# FRB_Simconex.net
KiCad netlist of a schematic drawn in Altium Designer
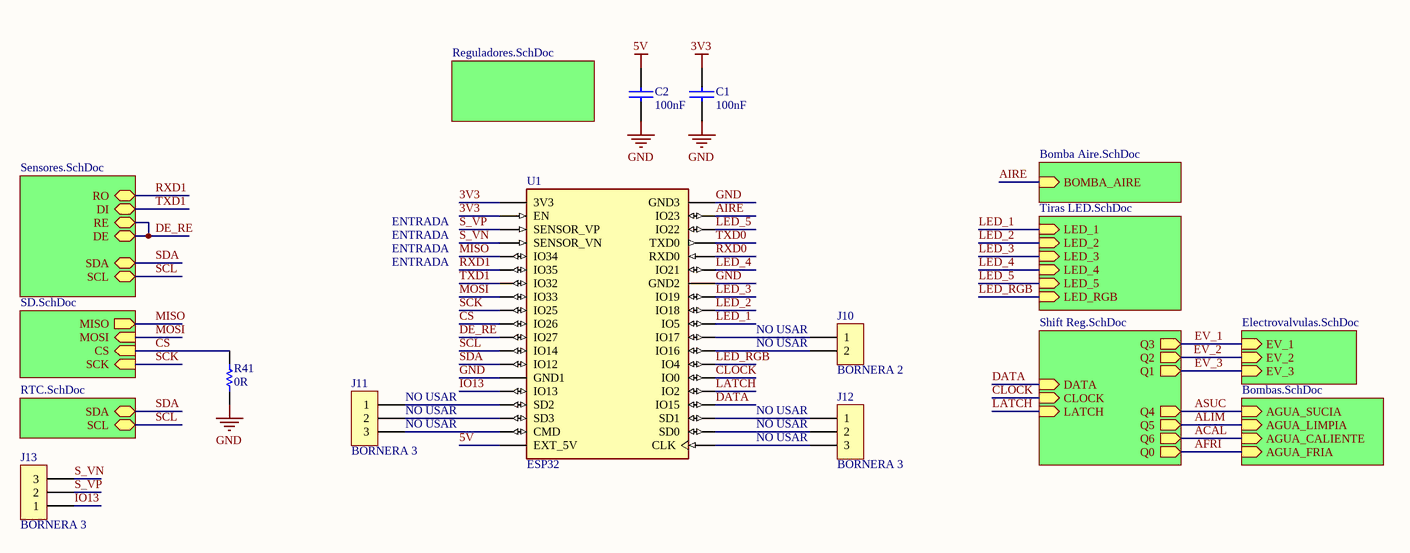
[diagram p0: FRB_Simconex.SchDoc]

(export (version "E")
  (design (tool "Eeschema 10.0.6"))
  (components
    (comp (ref "C1") (value "100nF") (footprint "0805") (libsource (lib "LIBPIOIX") (part "CAP")))
    (comp (ref "C2") (value "100nF") (footprint "0805") (libsource (lib "LIBPIOIX") (part "CAP")))
    (comp (ref "J10")
      (value "BORNERA 2")
      (footprint "BORNERA2")
      (libsource (lib "LIBPIOIX") (part "BORNERA 2"))
    )
    (comp (ref "J11") (value "BORNERA 3") (footprint "BORNERA3") (libsource (lib "") (part "BORNERA 3_2")))
    (comp (ref "J12")
      (value "BORNERA 3")
      (footprint "BORNERA3")
      (libsource (lib "LIBPIOIX") (part "BORNERA 3"))
    )
    (comp (ref "J13") (value "BORNERA 3") (footprint "BORNERA3") (libsource (lib "") (part "BORNERA 3_1")))
    (comp (ref "R41") (value "0R") (footprint "0805") (libsource (lib "LIBPIOIX") (part "RES")))
    (comp (ref "U1") (value "ESP32") (footprint "ESP32") (libsource (lib "Esquematicos") (part "ESP32")))
  )
  (nets
    (net (code "3") (name "/AIRE") (class "Default")
      (node (ref "U1") (pin "J3-2") (pinfunction "IO23_J3-2") (pintype "bidirectional"))
    )
    (net (code "6") (name "/CLOCK") (class "Default")
      (node (ref "U1") (pin "J3-14") (pinfunction "IO0_J3-14") (pintype "bidirectional"))
    )
    (net (code "7") (name "/CS") (class "Default")
      (node (ref "R41") (pin "2") (pinfunction "2_2") (pintype "passive"))
      (node (ref "U1") (pin "J2-10") (pinfunction "IO26_J2-10") (pintype "bidirectional"))
    )
    (net (code "8") (name "/DATA") (class "Default")
      (node (ref "U1") (pin "J3-16") (pinfunction "IO15_J3-16") (pintype "bidirectional"))
    )
    (net (code "9") (name "/DE_RE") (class "Default")
      (node (ref "U1") (pin "J2-11") (pinfunction "IO27_J2-11") (pintype "bidirectional"))
    )
    (net (code "13") (name "/IO13") (class "Default")
      (node (ref "J13") (pin "1") (pinfunction "1_1") (pintype "passive"))
      (node (ref "U1") (pin "J2-15") (pinfunction "IO13_J2-15") (pintype "bidirectional"))
    )
    (net (code "14") (name "/LATCH") (class "Default")
      (node (ref "U1") (pin "J3-15") (pinfunction "IO2_J3-15") (pintype "bidirectional"))
    )
    (net (code "15") (name "/LED_1") (class "Default")
      (node (ref "U1") (pin "J3-10") (pinfunction "IO5_J3-10") (pintype "bidirectional"))
    )
    (net (code "16") (name "/LED_2") (class "Default")
      (node (ref "U1") (pin "J3-9") (pinfunction "IO18_J3-9") (pintype "bidirectional"))
    )
    (net (code "17") (name "/LED_3") (class "Default")
      (node (ref "U1") (pin "J3-8") (pinfunction "IO19_J3-8") (pintype "bidirectional"))
    )
    (net (code "18") (name "/LED_4") (class "Default")
      (node (ref "U1") (pin "J3-6") (pinfunction "IO21_J3-6") (pintype "bidirectional"))
    )
    (net (code "19") (name "/LED_5") (class "Default")
      (node (ref "U1") (pin "J3-3") (pinfunction "IO22_J3-3") (pintype "bidirectional"))
    )
    (net (code "20") (name "/LED_RGB") (class "Default")
      (node (ref "U1") (pin "J3-13") (pinfunction "IO4_J3-13") (pintype "bidirectional"))
    )
    (net (code "21") (name "/MISO") (class "Default")
      (node (ref "U1") (pin "J2-5") (pinfunction "IO34_J2-5") (pintype "bidirectional"))
    )
    (net (code "22") (name "/MOSI") (class "Default")
      (node (ref "U1") (pin "J2-8") (pinfunction "IO33_J2-8") (pintype "bidirectional"))
    )
    (net (code "23") (name "/RXD0") (class "Default")
      (node (ref "U1") (pin "J3-5") (pinfunction "RXD0_J3-5") (pintype "input"))
    )
    (net (code "24") (name "/RXD1") (class "Default")
      (node (ref "U1") (pin "J2-6") (pinfunction "IO35_J2-6") (pintype "bidirectional"))
    )
    (net (code "25") (name "/SCK") (class "Default")
      (node (ref "U1") (pin "J2-9") (pinfunction "IO25_J2-9") (pintype "bidirectional"))
    )
    (net (code "26") (name "/SCL") (class "Default")
      (node (ref "U1") (pin "J2-12") (pinfunction "IO14_J2-12") (pintype "bidirectional"))
    )
    (net (code "27") (name "/SDA") (class "Default")
      (node (ref "U1") (pin "J2-13") (pinfunction "IO12_J2-13") (pintype "bidirectional"))
    )
    (net (code "28") (name "/S_VN") (class "Default")
      (node (ref "J13") (pin "3") (pinfunction "3_3") (pintype "passive"))
      (node (ref "U1") (pin "J2-4") (pinfunction "SENSOR_VN_J2-4") (pintype "input"))
    )
    (net (code "29") (name "/S_VP") (class "Default")
      (node (ref "J13") (pin "2") (pinfunction "2_2") (pintype "passive"))
      (node (ref "U1") (pin "J2-3") (pinfunction "SENSOR_VP_J2-3") (pintype "input"))
    )
    (net (code "30") (name "/TXD0") (class "Default")
      (node (ref "U1") (pin "J3-4") (pinfunction "TXD0_J3-4") (pintype "output"))
    )
    (net (code "31") (name "/TXD1") (class "Default")
      (node (ref "U1") (pin "J2-7") (pinfunction "IO32_J2-7") (pintype "bidirectional"))
    )
    (net (code "32") (name "3V3") (class "Default")
      (node (ref "C1") (pin "1") (pinfunction "1_1") (pintype "passive"))
      (node (ref "U1") (pin "J2-1") (pinfunction "3V3_J2-1") (pintype "power_in"))
      (node (ref "U1") (pin "J2-2") (pinfunction "EN_J2-2") (pintype "input"))
    )
    (net (code "33") (name "5V") (class "Default")
      (node (ref "C2") (pin "1") (pinfunction "1_1") (pintype "passive"))
      (node (ref "U1") (pin "J2-19") (pinfunction "EXT_5V_J2-19") (pintype "power_in"))
    )
    (net (code "34") (name "GND") (class "Default")
      (node (ref "C1") (pin "2") (pinfunction "2_2") (pintype "passive"))
      (node (ref "C2") (pin "2") (pinfunction "2_2") (pintype "passive"))
      (node (ref "R41") (pin "1") (pinfunction "1_1") (pintype "passive"))
      (node (ref "U1") (pin "J2-14") (pinfunction "GND1_J2-14") (pintype "power_in"))
      (node (ref "U1") (pin "J3-1") (pinfunction "GND3_J3-1") (pintype "power_in"))
      (node (ref "U1") (pin "J3-7") (pinfunction "GND2_J3-7") (pintype "power_in"))
    )
    (net (code "35") (name "Net-(U1-CLK)") (class "Default")
      (node (ref "J12") (pin "3") (pinfunction "3_3") (pintype "passive"))
      (node (ref "U1") (pin "J3-19") (pinfunction "CLK_J3-19") (pintype "input"))
    )
    (net (code "36") (name "Net-(U1-CMD)") (class "Default")
      (node (ref "J11") (pin "3") (pinfunction "3_3") (pintype "passive"))
      (node (ref "U1") (pin "J2-18") (pinfunction "CMD_J2-18") (pintype "bidirectional"))
    )
    (net (code "37") (name "Net-(U1-IO16)") (class "Default")
      (node (ref "J10") (pin "2") (pinfunction "2_2") (pintype "passive"))
      (node (ref "U1") (pin "J3-12") (pinfunction "IO16_J3-12") (pintype "bidirectional"))
    )
    (net (code "38") (name "Net-(U1-IO17)") (class "Default")
      (node (ref "J10") (pin "1") (pinfunction "1_1") (pintype "passive"))
      (node (ref "U1") (pin "J3-11") (pinfunction "IO17_J3-11") (pintype "bidirectional"))
    )
    (net (code "39") (name "Net-(U1-SD0)") (class "Default")
      (node (ref "J12") (pin "2") (pinfunction "2_2") (pintype "passive"))
      (node (ref "U1") (pin "J3-18") (pinfunction "SD0_J3-18") (pintype "bidirectional"))
    )
    (net (code "40") (name "Net-(U1-SD1)") (class "Default")
      (node (ref "J12") (pin "1") (pinfunction "1_1") (pintype "passive"))
      (node (ref "U1") (pin "J3-17") (pinfunction "SD1_J3-17") (pintype "bidirectional"))
    )
    (net (code "41") (name "Net-(U1-SD2)") (class "Default")
      (node (ref "J11") (pin "1") (pinfunction "1_1") (pintype "passive"))
      (node (ref "U1") (pin "J2-16") (pinfunction "SD2_J2-16") (pintype "bidirectional"))
    )
    (net (code "42") (name "Net-(U1-SD3)") (class "Default")
      (node (ref "J11") (pin "2") (pinfunction "2_2") (pintype "passive"))
      (node (ref "U1") (pin "J2-17") (pinfunction "SD3_J2-17") (pintype "bidirectional"))
    )
  )
)
